# 1_Power.net
KiCad netlist of a schematic drawn in Altium Designer
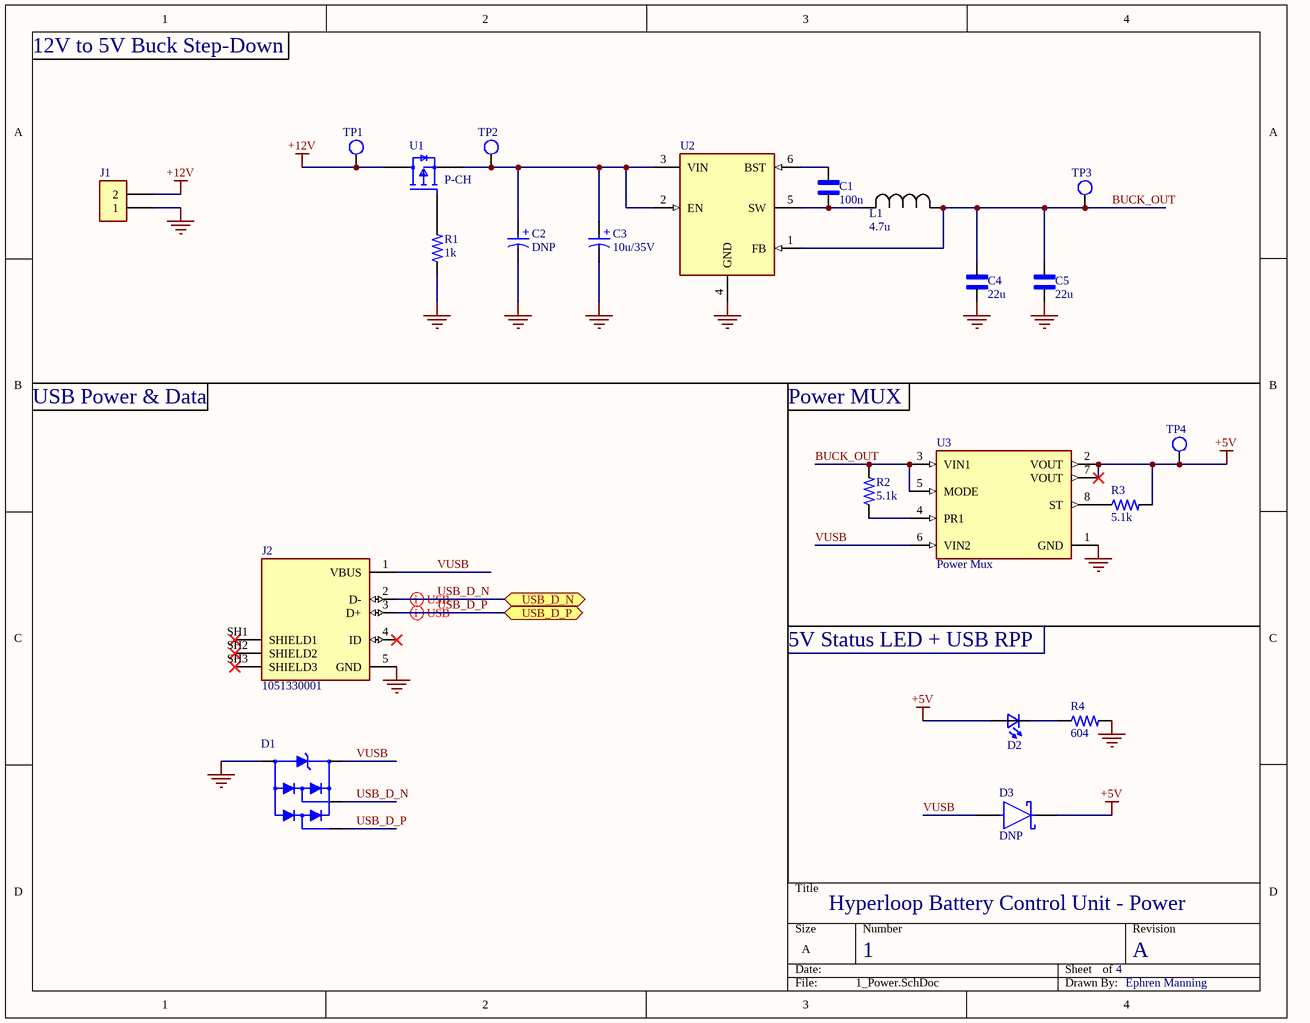
[diagram p0: 1_Power.SchDoc]

(export (version "E")
  (design (tool "Eeschema 10.0.6"))
  (components
    (comp (ref "C1")
      (value "100n")
      (footprint "CAP_0603-Footprint")
      (description "100nF/16V ±10% Ceramic 0603")
      (libsource (lib "SAE @ UIC Formula Electric") (part "CAP_0603-Symbol"))
    )
    (comp (ref "C2")
      (value "DNP")
      (footprint "WCAP-AS5H_D5H5.5")
      (description "ALUM 10uF 20% 35V SMD")
      (libsource (lib "SAE @ UIC Formula Electric") (part "Capacitor_Polarized"))
    )
    (comp (ref "C3")
      (value "10u/35V")
      (footprint "WCAP-AS5H_D5H5.5")
      (description "ALUM 10uF 20% 35V SMD")
      (libsource (lib "SAE @ UIC Formula Electric") (part "Capacitor_Polarized"))
    )
    (comp (ref "C4")
      (value "22u")
      (footprint "CAP_0603-Footprint")
      (description "22uF/10V CER 0603")
      (libsource (lib "SAE @ UIC Formula Electric") (part "CAP_0603-Symbol"))
    )
    (comp (ref "C5")
      (value "22u")
      (footprint "CAP_0603-Footprint")
      (description "22uF/10V CER 0603")
      (libsource (lib "SAE @ UIC Formula Electric") (part "CAP_0603-Symbol"))
    )
    (comp (ref "D1")
      (value "PRTR5V0U2X,215")
      (footprint "SOT143B")
      (description "Diode Array, ESD")
      (libsource (lib "SAE @ UIC Formula Electric") (part "PRTR5V0U2X,215"))
    )
    (comp (ref "D2")
      (value "LTST-C191KGKT")
      (footprint "LED_0603-Footprint-1")
      (description "Green 571nm LED Indication - Discrete 2V 0603 (1608 Metric)")
      (libsource (lib "SAE @ UIC Formula Electric") (part "LTST-C191KGKT"))
    )
    (comp (ref "D3")
      (value "DNP")
      (footprint "FP-SOD123W-MFG")
      (description "DIODE SCHOTTKY 60V 2A SOD123")
      (libsource (lib "SAE @ UIC Formula Electric") (part "1d6ec82d83fb6aee721767c19dac4b9"))
    )
    (comp (ref "J1")
      (value "282837-2")
      (footprint "TE_282837-2")
      (description "2x Screw Terminal")
      (libsource (lib "SAE @ UIC Formula Electric") (part "282837-2"))
    )
    (comp (ref "J2")
      (value "1051330001")
      (footprint "MOLEX_1051330001")
      (description "Micro USB Type B 90 Degree Conn")
      (libsource (lib "SAE @ UIC Formula Electric") (part "1051330001"))
    )
    (comp (ref "L1")
      (value "4.7u")
      (footprint "IND_SRP0412-1R0K_BRN")
      (description "4.7 uH 2.8A Inductor")
      (libsource (lib "SAE @ UIC Formula Electric") (part "SRP0415-4R7K"))
    )
    (comp (ref "R1")
      (value "1k")
      (footprint "RES_0603-Footprint-1")
      (description "1k 1% 0.1W 0603")
      (libsource (lib "SAE @ UIC Formula Electric") (part "0603_Res"))
    )
    (comp (ref "R2")
      (value "5.1k")
      (footprint "RES_0603-Footprint-1")
      (description "5.1k Ohms ±1% 0.1W 0603")
      (libsource (lib "SAE @ UIC Formula Electric") (part "0603_Res"))
    )
    (comp (ref "R3")
      (value "5.1k")
      (footprint "RES_0603-Footprint-1")
      (description "5.1k Ohms ±1% 0.1W 0603")
      (libsource (lib "SAE @ UIC Formula Electric") (part "0603_Res"))
    )
    (comp (ref "R4")
      (value "604")
      (footprint "RES_0603-Footprint-1")
      (description "604 Ohm 1% 1/10 W 0603")
      (libsource (lib "SAE @ UIC Formula Electric") (part "0603_Res"))
    )
    (comp (ref "TP1")
      (value "PTH Test Point")
      (footprint "PTH Test Point-Footprint-1")
      (description "Plated through-hole test point to allow soldering in pin headers.")
      (libsource (lib "SAE @ UIC Formula Electric") (part "PTH Test Point-Symbol-1"))
    )
    (comp (ref "TP2")
      (value "PTH Test Point")
      (footprint "PTH Test Point-Footprint-1")
      (description "Plated through-hole test point to allow soldering in pin headers.")
      (libsource (lib "SAE @ UIC Formula Electric") (part "PTH Test Point-Symbol-1"))
    )
    (comp (ref "TP3")
      (value "PTH Test Point")
      (footprint "PTH Test Point-Footprint-1")
      (description "Plated through-hole test point to allow soldering in pin headers.")
      (libsource (lib "SAE @ UIC Formula Electric") (part "PTH Test Point-Symbol-1"))
    )
    (comp (ref "TP4")
      (value "PTH Test Point")
      (footprint "PTH Test Point-Footprint-1")
      (description "Plated through-hole test point to allow soldering in pin headers.")
      (libsource (lib "SAE @ UIC Formula Electric") (part "PTH Test Point-Symbol-1"))
    )
    (comp (ref "U1")
      (value "P-CH")
      (footprint "SOT95P242X110-3N")
      (description "Mosfet P-CH 30V 3.8A Vgs(ON) = -10V SOT23")
      (libsource (lib "SAE @ UIC Formula Electric") (part "DMP3099L-7-Symbol-1"))
    )
    (comp (ref "U2")
      (value "AP63205WU-7")
      (footprint "FP-TSOT26-MFG")
      (description "AP63205 Series 32 V 2 A 1.1 MHz Synchronous Buck Converter -TSOT-26")
      (libsource (lib "SAE @ UIC Formula Electric") (part "AP63205WU-7"))
    )
    (comp (ref "U3")
      (value "Power Mux")
      (footprint "SOTFL50P160X60-8N")
      (description "TPS2116, Power Mux, 1.6V to 5.5V, 2.5A, SOT-583")
      (libsource (lib "SAE @ UIC Formula Electric") (part "TPS2116DRLR"))
    )
  )
  (nets
    (net (code "1") (name "+5V") (class "Default")
      (node (ref "D2") (pin "2") (pinfunction "A2_2") (pintype "passive"))
      (node (ref "D3") (pin "1") (pinfunction "1_1") (pintype "passive"))
      (node (ref "R3") (pin "2") (pinfunction "2_2") (pintype "passive"))
      (node (ref "TP4") (pin "1") (pinfunction "1_1") (pintype "passive"))
      (node (ref "U3") (pin "2") (pinfunction "VOUT_2") (pintype "output"))
      (node (ref "U3") (pin "7") (pinfunction "VOUT_7") (pintype "output"))
    )
    (net (code "2") (name "+12V") (class "Default")
      (node (ref "J1") (pin "2") (pinfunction "2_2") (pintype "passive"))
      (node (ref "TP1") (pin "1") (pinfunction "1_1") (pintype "passive"))
      (node (ref "U1") (pin "3") (pinfunction "Drain_3") (pintype "passive"))
    )
    (net (code "3") (name "/BUCK_OUT") (class "Default")
      (node (ref "C4") (pin "2") (pinfunction "2_2") (pintype "passive"))
      (node (ref "C5") (pin "2") (pinfunction "2_2") (pintype "passive"))
      (node (ref "L1") (pin "1") (pinfunction "1_1") (pintype "passive"))
      (node (ref "R2") (pin "2") (pinfunction "2_2") (pintype "passive"))
      (node (ref "TP3") (pin "1") (pinfunction "1_1") (pintype "passive"))
      (node (ref "U2") (pin "1") (pinfunction "FB_1") (pintype "input"))
      (node (ref "U3") (pin "3") (pinfunction "VIN1_3") (pintype "input"))
      (node (ref "U3") (pin "5") (pinfunction "MODE_5") (pintype "input"))
    )
    (net (code "4") (name "/USB_D_N") (class "Default")
      (node (ref "D1") (pin "2") (pinfunction "P$2_2") (pintype "passive"))
      (node (ref "J2") (pin "2") (pinfunction "D-_2") (pintype "bidirectional"))
    )
    (net (code "5") (name "/USB_D_P") (class "Default")
      (node (ref "D1") (pin "3") (pinfunction "P$3_3") (pintype "passive"))
      (node (ref "J2") (pin "3") (pinfunction "D+_3") (pintype "bidirectional"))
    )
    (net (code "6") (name "/VUSB") (class "Default")
      (node (ref "D1") (pin "4") (pinfunction "P$4_4") (pintype "passive"))
      (node (ref "D3") (pin "2") (pinfunction "2_2") (pintype "passive"))
      (node (ref "J2") (pin "1") (pinfunction "VBUS_1") (pintype "power_in"))
      (node (ref "U3") (pin "6") (pinfunction "VIN2_6") (pintype "input"))
    )
    (net (code "7") (name "GND") (class "Default")
      (node (ref "C2") (pin "2") (pinfunction "N_2") (pintype "passive"))
      (node (ref "C3") (pin "2") (pinfunction "N_2") (pintype "passive"))
      (node (ref "C4") (pin "1") (pinfunction "1_1") (pintype "passive"))
      (node (ref "C5") (pin "1") (pinfunction "1_1") (pintype "passive"))
      (node (ref "D1") (pin "1") (pinfunction "P$1_1") (pintype "passive"))
      (node (ref "J1") (pin "1") (pinfunction "1_1") (pintype "passive"))
      (node (ref "J2") (pin "5") (pinfunction "GND_5") (pintype "power_in"))
      (node (ref "R1") (pin "1") (pinfunction "1_1") (pintype "passive"))
      (node (ref "R4") (pin "2") (pinfunction "2_2") (pintype "passive"))
      (node (ref "U2") (pin "4") (pinfunction "GND_4") (pintype "power_in"))
      (node (ref "U3") (pin "1") (pinfunction "GND_1") (pintype "power_in"))
    )
    (net (code "8") (name "Net-(C2-P)") (class "Default")
      (node (ref "C2") (pin "1") (pinfunction "P_1") (pintype "passive"))
      (node (ref "C3") (pin "1") (pinfunction "P_1") (pintype "passive"))
      (node (ref "TP2") (pin "1") (pinfunction "1_1") (pintype "passive"))
      (node (ref "U1") (pin "2") (pinfunction "Source_2") (pintype "passive"))
      (node (ref "U2") (pin "2") (pinfunction "EN_2") (pintype "input"))
      (node (ref "U2") (pin "3") (pinfunction "VIN_3") (pintype "power_in"))
    )
    (net (code "9") (name "Net-(D2-K2)") (class "Default")
      (node (ref "D2") (pin "1") (pinfunction "K2_1") (pintype "passive"))
      (node (ref "R4") (pin "1") (pinfunction "1_1") (pintype "passive"))
    )
    (net (code "10") (name "Net-(U1-Gate)") (class "Default")
      (node (ref "R1") (pin "2") (pinfunction "2_2") (pintype "passive"))
      (node (ref "U1") (pin "1") (pinfunction "Gate_1") (pintype "passive"))
    )
    (net (code "11") (name "Net-(U2-BST)") (class "Default")
      (node (ref "C1") (pin "2") (pinfunction "2_2") (pintype "passive"))
      (node (ref "U2") (pin "6") (pinfunction "BST_6") (pintype "input"))
    )
    (net (code "12") (name "Net-(U2-SW)") (class "Default")
      (node (ref "C1") (pin "1") (pinfunction "1_1") (pintype "passive"))
      (node (ref "L1") (pin "2") (pinfunction "2_2") (pintype "passive"))
      (node (ref "U2") (pin "5") (pinfunction "SW_5") (pintype "power_in"))
    )
    (net (code "13") (name "Net-(U3-PR1)") (class "Default")
      (node (ref "R2") (pin "1") (pinfunction "1_1") (pintype "passive"))
      (node (ref "U3") (pin "4") (pinfunction "PR1_4") (pintype "input"))
    )
    (net (code "14") (name "Net-(U3-ST)") (class "Default")
      (node (ref "R3") (pin "1") (pinfunction "1_1") (pintype "passive"))
      (node (ref "U3") (pin "8") (pinfunction "ST_8") (pintype "output"))
    )
    (net (code "15") (name "unconnected-(J2-ID-Pad4)") (class "Default")
      (node (ref "J2") (pin "4") (pinfunction "ID_4") (pintype "bidirectional+no_connect"))
    )
    (net (code "16") (name "unconnected-(J2-SHIELD1-PadSH1)") (class "Default")
      (node (ref "J2") (pin "SH1") (pinfunction "SHIELD1_SH1") (pintype "passive+no_connect"))
    )
    (net (code "17") (name "unconnected-(J2-SHIELD2-PadSH2)") (class "Default")
      (node (ref "J2") (pin "SH2") (pinfunction "SHIELD2_SH2") (pintype "passive+no_connect"))
    )
    (net (code "18") (name "unconnected-(J2-SHIELD3-PadSH3)") (class "Default")
      (node (ref "J2") (pin "SH3") (pinfunction "SHIELD3_SH3") (pintype "passive+no_connect"))
    )
  )
)
